# design.net
KiCad netlist of a schematic drawn in EasyEDA Pro
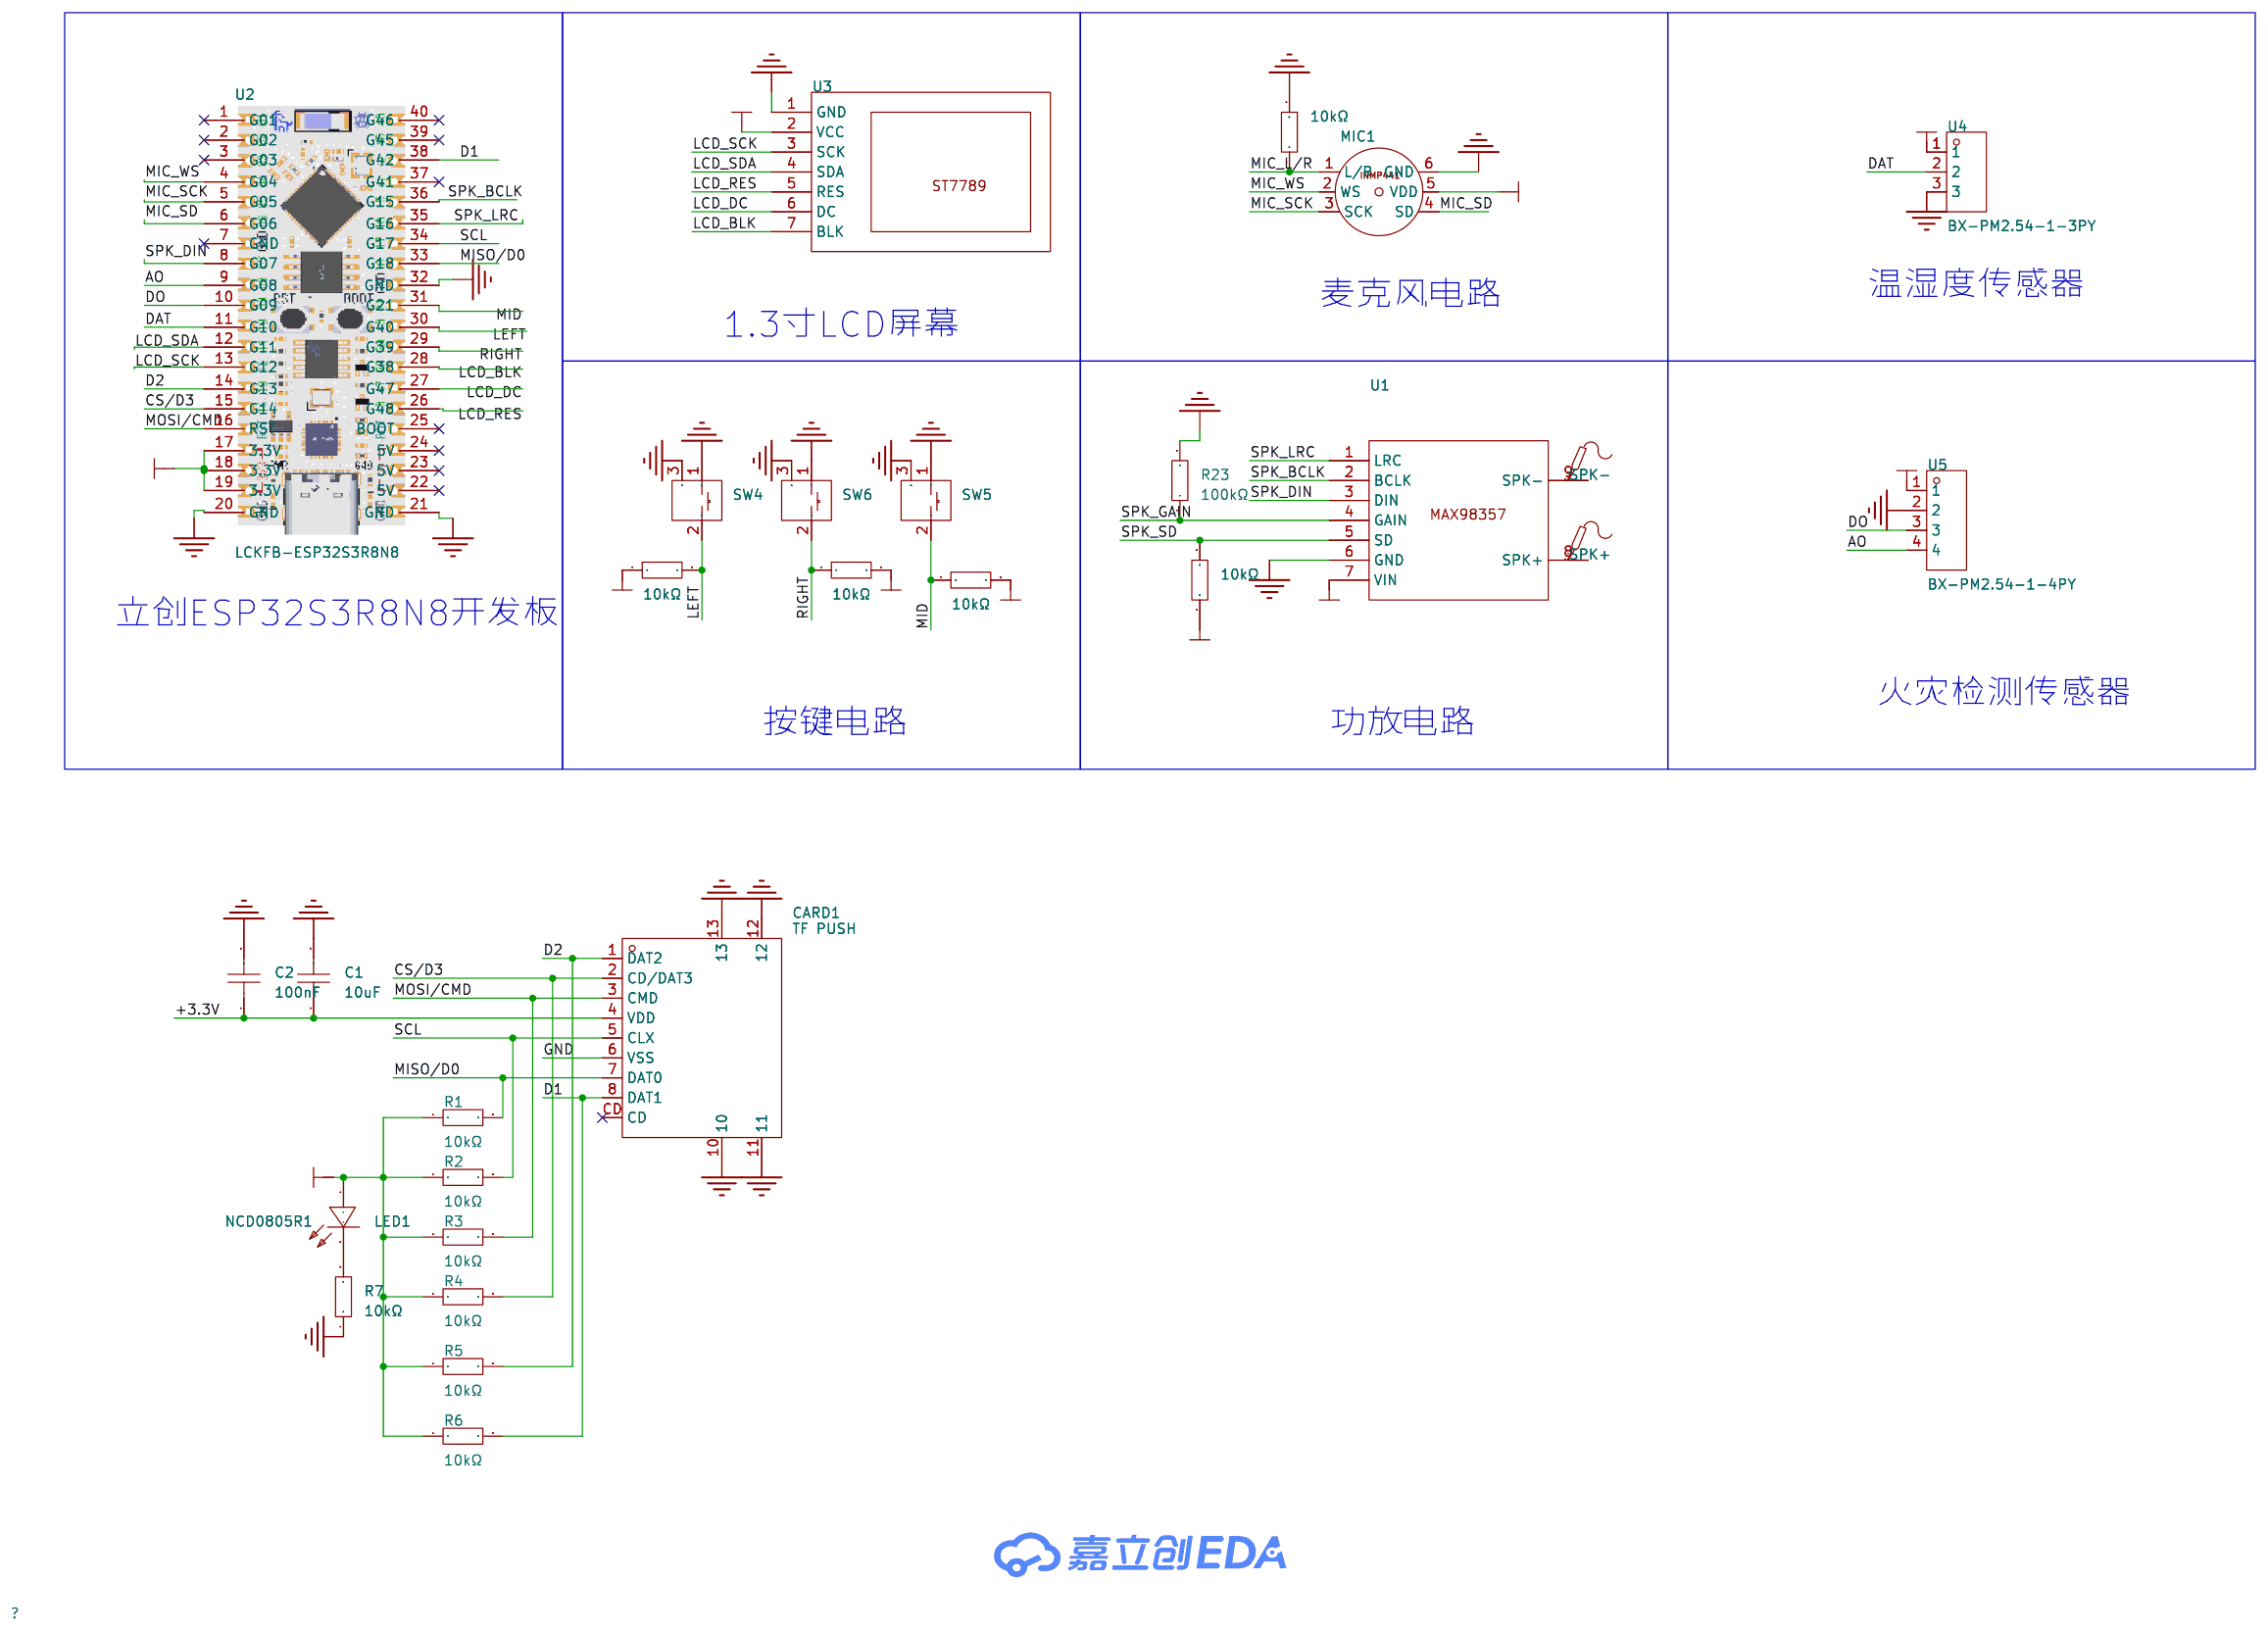
[diagram p0: schematic sheet]

(export (version "E")
  (design (tool "Eeschema 10.0.6"))
  (components
    (comp (ref "C1")
      (value "10uF")
      (footprint "easyedapro:C0805")
      (description "容值:10uF;精度:±10%;额定电压:25V;材质(温度系数):X5R;")
      (fields
        (field (name "Manufacturer Part") "CL21A106KAYNNNE")
        (field (name "Manufacturer") "SAMSUNG(三星)")
      )
      (libsource (lib "easyedapro") (part "CL21A106KAYNNNE"))
    )
    (comp (ref "C2")
      (value "100nF")
      (footprint "easyedapro:C0805")
      (description "容值:10uF;精度:±10%;额定电压:25V;材质(温度系数):X5R;")
      (fields
        (field (name "Manufacturer Part") "CL21A106KAYNNNE")
        (field (name "Manufacturer") "SAMSUNG(三星)")
      )
      (libsource (lib "easyedapro") (part "CL21A106KAYNNNE"))
    )
    (comp (ref "CARD1")
      (value "TF PUSH")
      (footprint "easyedapro:TF-SMD_TF-PUSH")
      (description "卡连接方式:自弹式;卡类型:MicroSD卡(TF卡);连接器类型:卡座;本体最大高度:2mm;触头材质:-;触头镀层:-;工作温度范围:-20°C~+90°C;焊接温度(最大值):-;")
      (fields (field (name "Manufacturer") "SHOU HAN(首韩)"))
      (libsource (lib "easyedapro") (part "TF PUSH"))
    )
    (comp (ref "LED1")
      (value "NCD0805R1")
      (footprint "easyedapro:LED0805-R-RD")
      (fields (field (name "Manufacturer") "国星光电"))
      (libsource (lib "easyedapro") (part "FC-2012HRK-620D"))
    )
    (comp (ref "MIC1")
      (value "~")
      (description "inmp441麦克风")
      (libsource (lib "easyedapro") (part "INMP441_Module"))
    )
    (comp (ref "R1")
      (value "10kΩ")
      (footprint "easyedapro:R0805")
      (description "电阻类型:厚膜电阻;阻值:1kΩ;精度:±1%;功率:125mW;最大工作电压:150V;温度系数:±100ppm/°C;")
      (fields
        (field (name "Manufacturer Part") "0805W8F1001T5E")
        (field (name "Manufacturer") "UNI-ROYAL(厚声)")
      )
      (libsource (lib "easyedapro") (part "0805W8F1001T5E"))
    )
    (comp (ref "R2")
      (value "10kΩ")
      (footprint "easyedapro:R0805")
      (description "电阻类型:厚膜电阻;阻值:1kΩ;精度:±1%;功率:125mW;最大工作电压:150V;温度系数:±100ppm/°C;")
      (fields
        (field (name "Manufacturer Part") "0805W8F1001T5E")
        (field (name "Manufacturer") "UNI-ROYAL(厚声)")
      )
      (libsource (lib "easyedapro") (part "0805W8F1001T5E"))
    )
    (comp (ref "R3")
      (value "10kΩ")
      (footprint "easyedapro:R0805")
      (description "电阻类型:厚膜电阻;阻值:1kΩ;精度:±1%;功率:125mW;最大工作电压:150V;温度系数:±100ppm/°C;")
      (fields
        (field (name "Manufacturer Part") "0805W8F1001T5E")
        (field (name "Manufacturer") "UNI-ROYAL(厚声)")
      )
      (libsource (lib "easyedapro") (part "0805W8F1001T5E"))
    )
    (comp (ref "R4")
      (value "10kΩ")
      (footprint "easyedapro:R0805")
      (description "电阻类型:厚膜电阻;阻值:1kΩ;精度:±1%;功率:125mW;最大工作电压:150V;温度系数:±100ppm/°C;")
      (fields
        (field (name "Manufacturer Part") "0805W8F1001T5E")
        (field (name "Manufacturer") "UNI-ROYAL(厚声)")
      )
      (libsource (lib "easyedapro") (part "0805W8F1001T5E"))
    )
    (comp (ref "R5")
      (value "10kΩ")
      (footprint "easyedapro:R0805")
      (description "电阻类型:厚膜电阻;阻值:1kΩ;精度:±1%;功率:125mW;最大工作电压:150V;温度系数:±100ppm/°C;")
      (fields
        (field (name "Manufacturer Part") "0805W8F1001T5E")
        (field (name "Manufacturer") "UNI-ROYAL(厚声)")
      )
      (libsource (lib "easyedapro") (part "0805W8F1001T5E"))
    )
    (comp (ref "R6")
      (value "10kΩ")
      (footprint "easyedapro:R0805")
      (description "电阻类型:厚膜电阻;阻值:1kΩ;精度:±1%;功率:125mW;最大工作电压:150V;温度系数:±100ppm/°C;")
      (fields
        (field (name "Manufacturer Part") "0805W8F1001T5E")
        (field (name "Manufacturer") "UNI-ROYAL(厚声)")
      )
      (libsource (lib "easyedapro") (part "0805W8F1001T5E"))
    )
    (comp (ref "R7")
      (value "10kΩ")
      (footprint "easyedapro:R0805")
      (description "电阻类型:厚膜电阻;阻值:1kΩ;精度:±1%;功率:125mW;最大工作电压:150V;温度系数:±100ppm/°C;")
      (fields
        (field (name "Manufacturer Part") "0805W8F1001T5E")
        (field (name "Manufacturer") "UNI-ROYAL(厚声)")
      )
      (libsource (lib "easyedapro") (part "0805W8F1001T5E"))
    )
    (comp (ref "R17")
      (value "10kΩ")
      (fields
        (field (name "Manufacturer Part") "RN1/4W10KFT/BA1")
        (field (name "Manufacturer") "Tyohm(幸亚电阻)")
      )
      (libsource (lib "easyedapro") (part "0805W8J0103T5E"))
    )
    (comp (ref "R18")
      (value "10kΩ")
      (fields
        (field (name "Manufacturer Part") "RN1/4W10KFT/BA1")
        (field (name "Manufacturer") "Tyohm(幸亚电阻)")
      )
      (libsource (lib "easyedapro") (part "0805W8J0103T5E"))
    )
    (comp (ref "R19")
      (value "10kΩ")
      (fields
        (field (name "Manufacturer Part") "RN1/4W10KFT/BA1")
        (field (name "Manufacturer") "Tyohm(幸亚电阻)")
      )
      (libsource (lib "easyedapro") (part "0805W8J0103T5E"))
    )
    (comp (ref "R20")
      (value "10kΩ")
      (fields
        (field (name "Manufacturer Part") "RN1/4W10KFT/BA1")
        (field (name "Manufacturer") "Tyohm(幸亚电阻)")
      )
      (libsource (lib "easyedapro") (part "0805W8J0103T5E"))
    )
    (comp (ref "R22")
      (value "10kΩ")
      (fields
        (field (name "Manufacturer Part") "RN1/4W10KFT/BA1")
        (field (name "Manufacturer") "Tyohm(幸亚电阻)")
      )
      (libsource (lib "easyedapro") (part "0805W8J0103T5E"))
    )
    (comp (ref "R23")
      (value "100kΩ")
      (footprint "easyedapro:RES-TH_BD2.4-L6.3-P10.30-D0.6")
      (description "电阻类型:金属膜电阻;阻值:100kΩ;精度:±5%;功率:250mW;")
      (fields (field (name "Manufacturer Part") "MFR-25JT-52-100K") (field (name "Manufacturer") "YAGEO(国巨)"))
      (libsource (lib "easyedapro") (part "MFR-25JT-52-100K"))
    )
    (comp (ref "SPK+")
      (value "~")
      (footprint "easyedapro:Test-Point-0.5mm")
      (description "Test Point 测试点")
      (libsource (lib "easyedapro") (part "Test-Point"))
    )
    (comp (ref "SPK-")
      (value "~")
      (footprint "easyedapro:Test-Point-0.5mm")
      (description "Test Point 测试点")
      (libsource (lib "easyedapro") (part "Test-Point"))
    )
    (comp (ref "SW4")
      (value "K2-1109DE-G4SW-04")
      (footprint "easyedapro:KEY-TH_3P-L4.5-W6.5-P3.00")
      (description "作用力:250gf;安装方式:卧插;开关长度:4.5mm;开关宽度:4.5mm;开关高度:6.5mm;触点电流:50mA;额定电压(DC):12V;绝缘电阻:100MΩ;机械寿命:10万次;")
      (fields (field (name "Manufacturer") "韩国韩荣"))
      (libsource (lib "easyedapro") (part "K2-1109DE-G4SW-04"))
    )
    (comp (ref "SW5")
      (value "K2-1109DE-G4SW-04")
      (footprint "easyedapro:KEY-TH_3P-L4.5-W6.5-P3.00")
      (description "作用力:250gf;安装方式:卧插;开关长度:4.5mm;开关宽度:4.5mm;开关高度:6.5mm;触点电流:50mA;额定电压(DC):12V;绝缘电阻:100MΩ;机械寿命:10万次;")
      (fields (field (name "Manufacturer") "韩国韩荣"))
      (libsource (lib "easyedapro") (part "K2-1109DE-G4SW-04"))
    )
    (comp (ref "SW6")
      (value "K2-1109DE-G4SW-04")
      (footprint "easyedapro:KEY-TH_3P-L4.5-W6.5-P3.00")
      (description "作用力:250gf;安装方式:卧插;开关长度:4.5mm;开关宽度:4.5mm;开关高度:6.5mm;触点电流:50mA;额定电压(DC):12V;绝缘电阻:100MΩ;机械寿命:10万次;")
      (fields (field (name "Manufacturer") "韩国韩荣"))
      (libsource (lib "easyedapro") (part "K2-1109DE-G4SW-04"))
    )
    (comp (ref "U1")
      (value "~")
      (footprint "easyedapro:MAX98357")
      (libsource (lib "easyedapro") (part "MAX98357"))
    )
    (comp (ref "U2")
      (value "LCKFB-ESP32S3R8N8")
      (footprint "easyedapro:DIP-40_L20.32-W51.66-P2.54-LS15.24")
      (fields (field (name "Manufacturer") "立创开发板"))
      (libsource (lib "easyedapro") (part "LCKFB-ESP32S3R8N8"))
    )
    (comp (ref "U3") (value "~") (description "LCD") (libsource (lib "easyedapro") (part "1.3寸LCD")))
    (comp (ref "U4")
      (value "BX-PM2.54-1-3PY")
      (footprint "easyedapro:HDR-TH_3P-P2.54-V-F")
      (fields (field (name "Manufacturer") "Bossie(博锡)"))
      (libsource (lib "easyedapro") (part "BX-PM2.54-1-3PY"))
    )
    (comp (ref "U5")
      (value "BX-PM2.54-1-4PY")
      (footprint "easyedapro:HDR-TH_4P-P2.54-V-F")
      (fields (field (name "Manufacturer") "Bossie(博锡)"))
      (libsource (lib "easyedapro") (part "BX-PM2.54-1-4PY"))
    )
  )
  (nets
    (net (code "1") (name "+3.3V") (class "Default")
      (node (ref "C1") (pin "1") (pinfunction "1_1") (pintype "unspecified"))
      (node (ref "C2") (pin "1") (pinfunction "1_1") (pintype "unspecified"))
      (node (ref "CARD1") (pin "4") (pinfunction "VDD_4") (pintype "unspecified"))
      (node (ref "LED1") (pin "1") (pinfunction "+_1") (pintype "unspecified"))
      (node (ref "MIC1") (pin "5") (pinfunction "VDD_5") (pintype "input"))
      (node (ref "R1") (pin "1") (pinfunction "1_1") (pintype "input"))
      (node (ref "R17") (pin "1") (pinfunction "1_1") (pintype "input"))
      (node (ref "R18") (pin "2") (pinfunction "2_2") (pintype "input"))
      (node (ref "R19") (pin "2") (pinfunction "2_2") (pintype "input"))
      (node (ref "R2") (pin "1") (pinfunction "1_1") (pintype "input"))
      (node (ref "R20") (pin "1") (pinfunction "1_1") (pintype "input"))
      (node (ref "R3") (pin "1") (pinfunction "1_1") (pintype "input"))
      (node (ref "R4") (pin "1") (pinfunction "1_1") (pintype "input"))
      (node (ref "R5") (pin "1") (pinfunction "1_1") (pintype "input"))
      (node (ref "R6") (pin "1") (pinfunction "1_1") (pintype "input"))
      (node (ref "U1") (pin "7") (pinfunction "VIN_7") (pintype "input"))
      (node (ref "U2") (pin "17") (pinfunction "3.3V_17") (pintype "unspecified"))
      (node (ref "U2") (pin "18") (pinfunction "3.3V_18") (pintype "unspecified"))
      (node (ref "U2") (pin "19") (pinfunction "3.3V_19") (pintype "unspecified"))
      (node (ref "U3") (pin "2") (pinfunction "VCC_2") (pintype "input"))
      (node (ref "U4") (pin "1") (pinfunction "1_1") (pintype "unspecified"))
      (node (ref "U5") (pin "1") (pinfunction "1_1") (pintype "unspecified"))
    )
    (net (code "2") (name "/AO") (class "Default")
      (node (ref "U2") (pin "9") (pinfunction "G08_9") (pintype "unspecified"))
      (node (ref "U5") (pin "4") (pinfunction "4_4") (pintype "unspecified"))
    )
    (net (code "3") (name "/CS{slash}D3") (class "Default")
      (node (ref "CARD1") (pin "2") (pinfunction "CD/DAT3_2") (pintype "unspecified"))
      (node (ref "R4") (pin "2") (pinfunction "2_2") (pintype "input"))
      (node (ref "U2") (pin "15") (pinfunction "G14_15") (pintype "unspecified"))
    )
    (net (code "4") (name "/D1") (class "Default")
      (node (ref "CARD1") (pin "8") (pinfunction "DAT1_8") (pintype "unspecified"))
      (node (ref "R6") (pin "2") (pinfunction "2_2") (pintype "input"))
      (node (ref "U2") (pin "38") (pinfunction "G42_38") (pintype "unspecified"))
    )
    (net (code "5") (name "/D2") (class "Default")
      (node (ref "CARD1") (pin "1") (pinfunction "DAT2_1") (pintype "unspecified"))
      (node (ref "R5") (pin "2") (pinfunction "2_2") (pintype "input"))
      (node (ref "U2") (pin "14") (pinfunction "G13_14") (pintype "unspecified"))
    )
    (net (code "6") (name "/DAT") (class "Default")
      (node (ref "U2") (pin "11") (pinfunction "G10_11") (pintype "unspecified"))
      (node (ref "U4") (pin "2") (pinfunction "2_2") (pintype "unspecified"))
    )
    (net (code "7") (name "/DO") (class "Default")
      (node (ref "U2") (pin "10") (pinfunction "G09_10") (pintype "unspecified"))
      (node (ref "U5") (pin "3") (pinfunction "3_3") (pintype "unspecified"))
    )
    (net (code "8") (name "/LCD_BLK") (class "Default")
      (node (ref "U2") (pin "28") (pinfunction "G38_28") (pintype "unspecified"))
      (node (ref "U3") (pin "7") (pinfunction "BLK_7") (pintype "input"))
    )
    (net (code "9") (name "/LCD_DC") (class "Default")
      (node (ref "U2") (pin "27") (pinfunction "G47_27") (pintype "unspecified"))
      (node (ref "U3") (pin "6") (pinfunction "DC_6") (pintype "input"))
    )
    (net (code "10") (name "/LCD_RES") (class "Default")
      (node (ref "U2") (pin "26") (pinfunction "G48_26") (pintype "unspecified"))
      (node (ref "U3") (pin "5") (pinfunction "RES_5") (pintype "input"))
    )
    (net (code "11") (name "/LCD_SCK") (class "Default")
      (node (ref "U2") (pin "13") (pinfunction "G12_13") (pintype "unspecified"))
      (node (ref "U3") (pin "3") (pinfunction "SCK_3") (pintype "input"))
    )
    (net (code "12") (name "/LCD_SDA") (class "Default")
      (node (ref "U2") (pin "12") (pinfunction "G11_12") (pintype "unspecified"))
      (node (ref "U3") (pin "4") (pinfunction "SDA_4") (pintype "input"))
    )
    (net (code "13") (name "/LEFT") (class "Default")
      (node (ref "R17") (pin "2") (pinfunction "2_2") (pintype "input"))
      (node (ref "SW4") (pin "2") (pinfunction "2_2") (pintype "unspecified"))
      (node (ref "U2") (pin "30") (pinfunction "G40_30") (pintype "unspecified"))
    )
    (net (code "14") (name "/MIC_L{slash}R") (class "Default")
      (node (ref "MIC1") (pin "1") (pinfunction "L/R_1") (pintype "input"))
      (node (ref "R22") (pin "1") (pinfunction "1_1") (pintype "input"))
    )
    (net (code "15") (name "/MIC_SCK") (class "Default")
      (node (ref "MIC1") (pin "3") (pinfunction "SCK_3") (pintype "input"))
      (node (ref "U2") (pin "5") (pinfunction "G05_5") (pintype "unspecified"))
    )
    (net (code "16") (name "/MIC_SD") (class "Default")
      (node (ref "MIC1") (pin "4") (pinfunction "SD_4") (pintype "input"))
      (node (ref "U2") (pin "6") (pinfunction "G06_6") (pintype "unspecified"))
    )
    (net (code "17") (name "/MIC_WS") (class "Default")
      (node (ref "MIC1") (pin "2") (pinfunction "WS_2") (pintype "input"))
      (node (ref "U2") (pin "4") (pinfunction "G04_4") (pintype "unspecified"))
    )
    (net (code "18") (name "/MID") (class "Default")
      (node (ref "R19") (pin "1") (pinfunction "1_1") (pintype "input"))
      (node (ref "SW5") (pin "2") (pinfunction "2_2") (pintype "unspecified"))
      (node (ref "U2") (pin "31") (pinfunction "G21_31") (pintype "unspecified"))
    )
    (net (code "19") (name "/MISO{slash}D0") (class "Default")
      (node (ref "CARD1") (pin "7") (pinfunction "DAT0_7") (pintype "unspecified"))
      (node (ref "R1") (pin "2") (pinfunction "2_2") (pintype "input"))
      (node (ref "U2") (pin "33") (pinfunction "G18_33") (pintype "unspecified"))
    )
    (net (code "20") (name "/MOSI{slash}CMD") (class "Default")
      (node (ref "CARD1") (pin "3") (pinfunction "CMD_3") (pintype "unspecified"))
      (node (ref "R3") (pin "2") (pinfunction "2_2") (pintype "input"))
      (node (ref "U2") (pin "16") (pinfunction "RST_16") (pintype "unspecified"))
    )
    (net (code "21") (name "/RIGHT") (class "Default")
      (node (ref "R18") (pin "1") (pinfunction "1_1") (pintype "input"))
      (node (ref "SW6") (pin "2") (pinfunction "2_2") (pintype "unspecified"))
      (node (ref "U2") (pin "29") (pinfunction "G39_29") (pintype "unspecified"))
    )
    (net (code "22") (name "/SCL") (class "Default")
      (node (ref "CARD1") (pin "5") (pinfunction "CLX_5") (pintype "unspecified"))
      (node (ref "R2") (pin "2") (pinfunction "2_2") (pintype "input"))
      (node (ref "U2") (pin "34") (pinfunction "G17_34") (pintype "unspecified"))
    )
    (net (code "23") (name "/SPK_BCLK") (class "Default")
      (node (ref "U1") (pin "2") (pinfunction "BCLK_2") (pintype "input"))
      (node (ref "U2") (pin "36") (pinfunction "G15_36") (pintype "unspecified"))
    )
    (net (code "24") (name "/SPK_DIN") (class "Default")
      (node (ref "U1") (pin "3") (pinfunction "DIN_3") (pintype "input"))
      (node (ref "U2") (pin "8") (pinfunction "G07_8") (pintype "unspecified"))
    )
    (net (code "25") (name "/SPK_GAIN") (class "Default")
      (node (ref "R23") (pin "1") (pinfunction "1_1") (pintype "unspecified"))
      (node (ref "U1") (pin "4") (pinfunction "GAIN_4") (pintype "input"))
    )
    (net (code "26") (name "/SPK_LRC") (class "Default")
      (node (ref "U1") (pin "1") (pinfunction "LRC_1") (pintype "input"))
      (node (ref "U2") (pin "35") (pinfunction "G16_35") (pintype "unspecified"))
    )
    (net (code "27") (name "/SPK_SD") (class "Default")
      (node (ref "R20") (pin "2") (pinfunction "2_2") (pintype "input"))
      (node (ref "U1") (pin "5") (pinfunction "SD_5") (pintype "input"))
    )
    (net (code "28") (name "GND") (class "Default")
      (node (ref "C1") (pin "2") (pinfunction "2_2") (pintype "unspecified"))
      (node (ref "C2") (pin "2") (pinfunction "2_2") (pintype "unspecified"))
      (node (ref "CARD1") (pin "10") (pinfunction "10_10") (pintype "unspecified"))
      (node (ref "CARD1") (pin "11") (pinfunction "11_11") (pintype "unspecified"))
      (node (ref "CARD1") (pin "12") (pinfunction "12_12") (pintype "unspecified"))
      (node (ref "CARD1") (pin "13") (pinfunction "13_13") (pintype "unspecified"))
      (node (ref "CARD1") (pin "6") (pinfunction "VSS_6") (pintype "unspecified"))
      (node (ref "MIC1") (pin "6") (pinfunction "GND_6") (pintype "input"))
      (node (ref "R22") (pin "2") (pinfunction "2_2") (pintype "input"))
      (node (ref "R23") (pin "2") (pinfunction "2_2") (pintype "unspecified"))
      (node (ref "R7") (pin "1") (pinfunction "1_1") (pintype "input"))
      (node (ref "SW4") (pin "1") (pinfunction "1_1") (pintype "unspecified"))
      (node (ref "SW4") (pin "3") (pinfunction "3_3") (pintype "unspecified"))
      (node (ref "SW5") (pin "1") (pinfunction "1_1") (pintype "unspecified"))
      (node (ref "SW5") (pin "3") (pinfunction "3_3") (pintype "unspecified"))
      (node (ref "SW6") (pin "1") (pinfunction "1_1") (pintype "unspecified"))
      (node (ref "SW6") (pin "3") (pinfunction "3_3") (pintype "unspecified"))
      (node (ref "U1") (pin "6") (pinfunction "GND_6") (pintype "input"))
      (node (ref "U2") (pin "20") (pinfunction "GND_20") (pintype "unspecified"))
      (node (ref "U2") (pin "21") (pinfunction "GND_21") (pintype "unspecified"))
      (node (ref "U2") (pin "32") (pinfunction "GND_32") (pintype "unspecified"))
      (node (ref "U3") (pin "1") (pinfunction "GND_1") (pintype "input"))
      (node (ref "U4") (pin "3") (pinfunction "3_3") (pintype "unspecified"))
      (node (ref "U5") (pin "2") (pinfunction "2_2") (pintype "unspecified"))
    )
    (net (code "29") (name "Net-(LED1--)") (class "Default")
      (node (ref "LED1") (pin "2") (pinfunction "-_2") (pintype "unspecified"))
      (node (ref "R7") (pin "2") (pinfunction "2_2") (pintype "input"))
    )
    (net (code "30") (name "Net-(U1-SPK+)") (class "Default")
      (node (ref "SPK+") (pin "1") (pinfunction "1_1") (pintype "input"))
      (node (ref "U1") (pin "8") (pinfunction "SPK+_8") (pintype "input"))
    )
    (net (code "31") (name "Net-(U1-SPK-)") (class "Default")
      (node (ref "SPK-") (pin "1") (pinfunction "1_1") (pintype "input"))
      (node (ref "U1") (pin "9") (pinfunction "SPK-_9") (pintype "input"))
    )
    (net (code "32") (name "unconnected-(CARD1-PadCD)") (class "Default")
      (node (ref "CARD1") (pin "CD") (pinfunction "CD_CD") (pintype "unspecified+no_connect"))
    )
    (net (code "33") (name "unconnected-(U2-5V-Pad22)") (class "Default")
      (node (ref "U2") (pin "22") (pinfunction "5V_22") (pintype "unspecified+no_connect"))
    )
    (net (code "34") (name "unconnected-(U2-5V-Pad23)") (class "Default")
      (node (ref "U2") (pin "23") (pinfunction "5V_23") (pintype "unspecified+no_connect"))
    )
    (net (code "35") (name "unconnected-(U2-5V-Pad24)") (class "Default")
      (node (ref "U2") (pin "24") (pinfunction "5V_24") (pintype "unspecified+no_connect"))
    )
    (net (code "36") (name "unconnected-(U2-BOOT-Pad25)") (class "Default")
      (node (ref "U2") (pin "25") (pinfunction "BOOT_25") (pintype "unspecified+no_connect"))
    )
    (net (code "37") (name "unconnected-(U2-G01-Pad1)") (class "Default")
      (node (ref "U2") (pin "1") (pinfunction "G01_1") (pintype "unspecified+no_connect"))
    )
    (net (code "38") (name "unconnected-(U2-G02-Pad2)") (class "Default")
      (node (ref "U2") (pin "2") (pinfunction "G02_2") (pintype "unspecified+no_connect"))
    )
    (net (code "39") (name "unconnected-(U2-G03-Pad3)") (class "Default")
      (node (ref "U2") (pin "3") (pinfunction "G03_3") (pintype "unspecified+no_connect"))
    )
    (net (code "40") (name "unconnected-(U2-G41-Pad37)") (class "Default")
      (node (ref "U2") (pin "37") (pinfunction "G41_37") (pintype "unspecified+no_connect"))
    )
    (net (code "41") (name "unconnected-(U2-G45-Pad39)") (class "Default")
      (node (ref "U2") (pin "39") (pinfunction "G45_39") (pintype "unspecified+no_connect"))
    )
    (net (code "42") (name "unconnected-(U2-G46-Pad40)") (class "Default")
      (node (ref "U2") (pin "40") (pinfunction "G46_40") (pintype "unspecified+no_connect"))
    )
    (net (code "43") (name "unconnected-(U2-GND-Pad7)") (class "Default")
      (node (ref "U2") (pin "7") (pinfunction "GND_7") (pintype "unspecified+no_connect"))
    )
  )
)
